# MicroD_MEC5_Adapter.net
KiCad netlist of a schematic drawn in Altium Designer
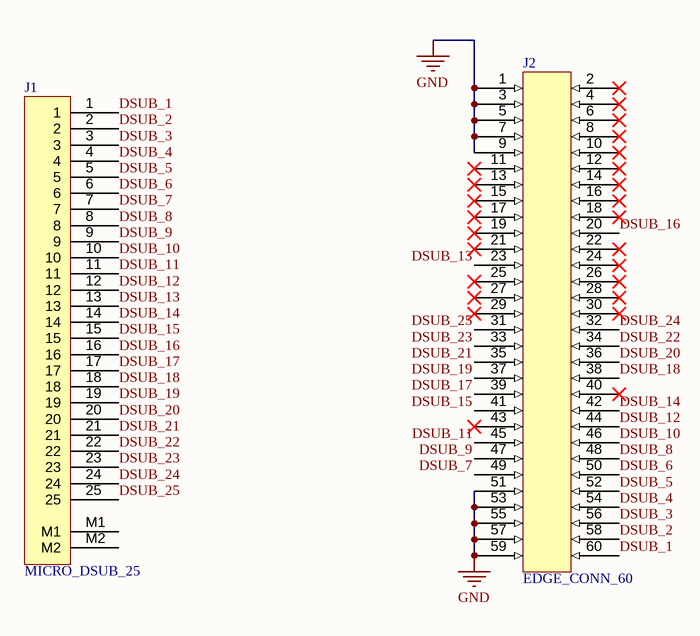
[diagram p0: MicroD_MEC5_Adapter.SchDoc]

(export (version "E")
  (design (tool "Eeschema 10.0.6"))
  (components
    (comp (ref "J1")
      (value "MICRO_DSUB_25")
      (footprint "581-M25-213L461")
      (description "Micro D-Sub 25 pin connector")
      (libsource (lib "Connectors") (part "MICRO_DSUB_25"))
    )
    (comp (ref "J2")
      (value "EDGE_CONN_60")
      (footprint "EDGE_CONN_60")
      (description "Card edge connector 60-pin")
      (libsource (lib "Connectors") (part "EDGE_CONN_60"))
    )
  )
  (nets
    (net (code "1") (name "/DSUB_1") (class "Default")
      (node (ref "J1") (pin "1") (pinfunction "1_1") (pintype "passive"))
      (node (ref "J2") (pin "60") (pintype "input"))
    )
    (net (code "2") (name "/DSUB_2") (class "Default")
      (node (ref "J1") (pin "2") (pinfunction "2_2") (pintype "passive"))
      (node (ref "J2") (pin "58") (pintype "input"))
    )
    (net (code "3") (name "/DSUB_3") (class "Default")
      (node (ref "J1") (pin "3") (pinfunction "3_3") (pintype "passive"))
      (node (ref "J2") (pin "56") (pintype "input"))
    )
    (net (code "4") (name "/DSUB_4") (class "Default")
      (node (ref "J1") (pin "4") (pinfunction "4_4") (pintype "passive"))
      (node (ref "J2") (pin "54") (pintype "input"))
    )
    (net (code "5") (name "/DSUB_5") (class "Default")
      (node (ref "J1") (pin "5") (pinfunction "5_5") (pintype "passive"))
      (node (ref "J2") (pin "52") (pintype "input"))
    )
    (net (code "6") (name "/DSUB_6") (class "Default")
      (node (ref "J1") (pin "6") (pinfunction "6_6") (pintype "passive"))
      (node (ref "J2") (pin "50") (pintype "input"))
    )
    (net (code "7") (name "/DSUB_7") (class "Default")
      (node (ref "J1") (pin "7") (pinfunction "7_7") (pintype "passive"))
      (node (ref "J2") (pin "49") (pintype "input"))
    )
    (net (code "8") (name "/DSUB_8") (class "Default")
      (node (ref "J1") (pin "8") (pinfunction "8_8") (pintype "passive"))
      (node (ref "J2") (pin "48") (pintype "input"))
    )
    (net (code "9") (name "/DSUB_9") (class "Default")
      (node (ref "J1") (pin "9") (pinfunction "9_9") (pintype "passive"))
      (node (ref "J2") (pin "47") (pintype "input"))
    )
    (net (code "10") (name "/DSUB_10") (class "Default")
      (node (ref "J1") (pin "10") (pinfunction "10_10") (pintype "passive"))
      (node (ref "J2") (pin "46") (pintype "input"))
    )
    (net (code "11") (name "/DSUB_11") (class "Default")
      (node (ref "J1") (pin "11") (pinfunction "11_11") (pintype "passive"))
      (node (ref "J2") (pin "45") (pintype "input"))
    )
    (net (code "12") (name "/DSUB_12") (class "Default")
      (node (ref "J1") (pin "12") (pinfunction "12_12") (pintype "passive"))
      (node (ref "J2") (pin "44") (pintype "input"))
    )
    (net (code "13") (name "/DSUB_13") (class "Default")
      (node (ref "J1") (pin "13") (pinfunction "13_13") (pintype "passive"))
      (node (ref "J2") (pin "23") (pintype "input"))
    )
    (net (code "14") (name "/DSUB_14") (class "Default")
      (node (ref "J1") (pin "14") (pinfunction "14_14") (pintype "passive"))
      (node (ref "J2") (pin "42") (pintype "input"))
    )
    (net (code "15") (name "/DSUB_15") (class "Default")
      (node (ref "J1") (pin "15") (pinfunction "15_15") (pintype "passive"))
      (node (ref "J2") (pin "41") (pintype "input"))
    )
    (net (code "16") (name "/DSUB_16") (class "Default")
      (node (ref "J1") (pin "16") (pinfunction "16_16") (pintype "passive"))
      (node (ref "J2") (pin "20") (pintype "input"))
    )
    (net (code "17") (name "/DSUB_17") (class "Default")
      (node (ref "J1") (pin "17") (pinfunction "17_17") (pintype "passive"))
      (node (ref "J2") (pin "39") (pintype "input"))
    )
    (net (code "18") (name "/DSUB_18") (class "Default")
      (node (ref "J1") (pin "18") (pinfunction "18_18") (pintype "passive"))
      (node (ref "J2") (pin "38") (pintype "input"))
    )
    (net (code "19") (name "/DSUB_19") (class "Default")
      (node (ref "J1") (pin "19") (pinfunction "19_19") (pintype "passive"))
      (node (ref "J2") (pin "37") (pintype "input"))
    )
    (net (code "20") (name "/DSUB_20") (class "Default")
      (node (ref "J1") (pin "20") (pinfunction "20_20") (pintype "passive"))
      (node (ref "J2") (pin "36") (pintype "input"))
    )
    (net (code "21") (name "/DSUB_21") (class "Default")
      (node (ref "J1") (pin "21") (pinfunction "21_21") (pintype "passive"))
      (node (ref "J2") (pin "35") (pintype "input"))
    )
    (net (code "22") (name "/DSUB_22") (class "Default")
      (node (ref "J1") (pin "22") (pinfunction "22_22") (pintype "passive"))
      (node (ref "J2") (pin "34") (pintype "input"))
    )
    (net (code "23") (name "/DSUB_23") (class "Default")
      (node (ref "J1") (pin "23") (pinfunction "23_23") (pintype "passive"))
      (node (ref "J2") (pin "33") (pintype "input"))
    )
    (net (code "24") (name "/DSUB_24") (class "Default")
      (node (ref "J1") (pin "24") (pinfunction "24_24") (pintype "passive"))
      (node (ref "J2") (pin "32") (pintype "input"))
    )
    (net (code "25") (name "/DSUB_25") (class "Default")
      (node (ref "J1") (pin "25") (pinfunction "25_25") (pintype "passive"))
      (node (ref "J2") (pin "31") (pintype "input"))
    )
    (net (code "26") (name "GND") (class "Default")
      (node (ref "J2") (pin "1") (pintype "input"))
      (node (ref "J2") (pin "3") (pintype "input"))
      (node (ref "J2") (pin "5") (pintype "input"))
      (node (ref "J2") (pin "51") (pintype "input"))
      (node (ref "J2") (pin "53") (pintype "input"))
      (node (ref "J2") (pin "55") (pintype "input"))
      (node (ref "J2") (pin "57") (pintype "input"))
      (node (ref "J2") (pin "59") (pintype "input"))
      (node (ref "J2") (pin "7") (pintype "input"))
      (node (ref "J2") (pin "9") (pintype "input"))
    )
    (net (code "27") (name "unconnected-(J1-PadM1)") (class "Default")
      (node (ref "J1") (pin "M1") (pinfunction "M1_M1") (pintype "passive"))
    )
    (net (code "28") (name "unconnected-(J1-PadM2)") (class "Default")
      (node (ref "J1") (pin "M2") (pinfunction "M2_M2") (pintype "passive"))
    )
    (net (code "29") (name "unconnected-(J2-Pad2)") (class "Default")
      (node (ref "J2") (pin "2") (pintype "input+no_connect"))
    )
    (net (code "30") (name "unconnected-(J2-Pad4)") (class "Default")
      (node (ref "J2") (pin "4") (pintype "input+no_connect"))
    )
    (net (code "31") (name "unconnected-(J2-Pad6)") (class "Default")
      (node (ref "J2") (pin "6") (pintype "input+no_connect"))
    )
    (net (code "32") (name "unconnected-(J2-Pad8)") (class "Default")
      (node (ref "J2") (pin "8") (pintype "input+no_connect"))
    )
    (net (code "33") (name "unconnected-(J2-Pad10)") (class "Default")
      (node (ref "J2") (pin "10") (pintype "input+no_connect"))
    )
    (net (code "34") (name "unconnected-(J2-Pad11)") (class "Default")
      (node (ref "J2") (pin "11") (pintype "input+no_connect"))
    )
    (net (code "35") (name "unconnected-(J2-Pad12)") (class "Default")
      (node (ref "J2") (pin "12") (pintype "input+no_connect"))
    )
    (net (code "36") (name "unconnected-(J2-Pad13)") (class "Default")
      (node (ref "J2") (pin "13") (pintype "input+no_connect"))
    )
    (net (code "37") (name "unconnected-(J2-Pad14)") (class "Default")
      (node (ref "J2") (pin "14") (pintype "input+no_connect"))
    )
    (net (code "38") (name "unconnected-(J2-Pad15)") (class "Default")
      (node (ref "J2") (pin "15") (pintype "input+no_connect"))
    )
    (net (code "39") (name "unconnected-(J2-Pad16)") (class "Default")
      (node (ref "J2") (pin "16") (pintype "input+no_connect"))
    )
    (net (code "40") (name "unconnected-(J2-Pad17)") (class "Default")
      (node (ref "J2") (pin "17") (pintype "input+no_connect"))
    )
    (net (code "41") (name "unconnected-(J2-Pad18)") (class "Default")
      (node (ref "J2") (pin "18") (pintype "input+no_connect"))
    )
    (net (code "42") (name "unconnected-(J2-Pad19)") (class "Default")
      (node (ref "J2") (pin "19") (pintype "input+no_connect"))
    )
    (net (code "43") (name "unconnected-(J2-Pad21)") (class "Default")
      (node (ref "J2") (pin "21") (pintype "input+no_connect"))
    )
    (net (code "44") (name "unconnected-(J2-Pad22)") (class "Default")
      (node (ref "J2") (pin "22") (pintype "input+no_connect"))
    )
    (net (code "45") (name "unconnected-(J2-Pad24)") (class "Default")
      (node (ref "J2") (pin "24") (pintype "input+no_connect"))
    )
    (net (code "46") (name "unconnected-(J2-Pad25)") (class "Default")
      (node (ref "J2") (pin "25") (pintype "input+no_connect"))
    )
    (net (code "47") (name "unconnected-(J2-Pad26)") (class "Default")
      (node (ref "J2") (pin "26") (pintype "input+no_connect"))
    )
    (net (code "48") (name "unconnected-(J2-Pad27)") (class "Default")
      (node (ref "J2") (pin "27") (pintype "input+no_connect"))
    )
    (net (code "49") (name "unconnected-(J2-Pad28)") (class "Default")
      (node (ref "J2") (pin "28") (pintype "input+no_connect"))
    )
    (net (code "50") (name "unconnected-(J2-Pad29)") (class "Default")
      (node (ref "J2") (pin "29") (pintype "input+no_connect"))
    )
    (net (code "51") (name "unconnected-(J2-Pad30)") (class "Default")
      (node (ref "J2") (pin "30") (pintype "input+no_connect"))
    )
    (net (code "52") (name "unconnected-(J2-Pad40)") (class "Default")
      (node (ref "J2") (pin "40") (pintype "input+no_connect"))
    )
    (net (code "53") (name "unconnected-(J2-Pad43)") (class "Default")
      (node (ref "J2") (pin "43") (pintype "input+no_connect"))
    )
  )
)
